# photodiode.net
KiCad netlist of a schematic drawn in EAGLE
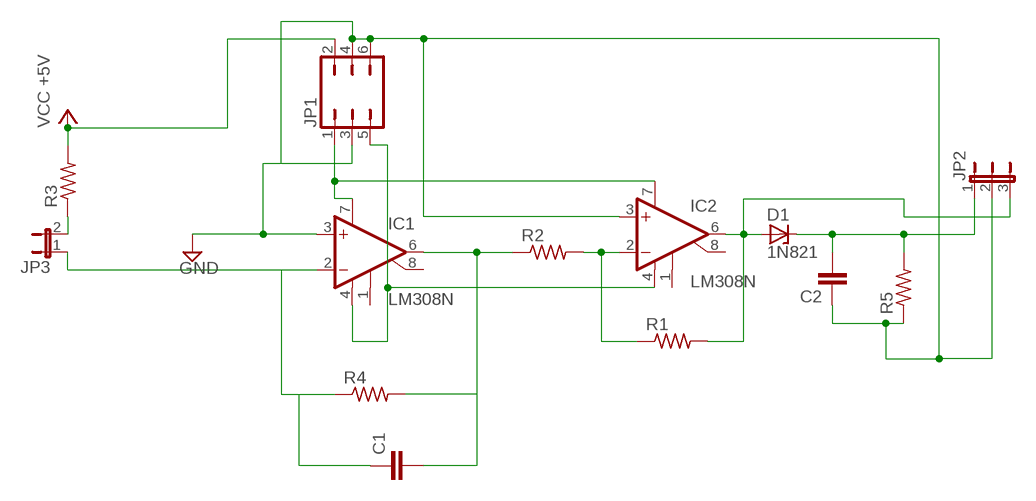
[diagram p0: schematic, sheet 1]

(export (version "E")
  (design (tool "Eeschema 10.0.6"))
  (components
    (comp (ref "C1")
      (value "C-EU025-024X044")
      (footprint "eagle-import:C025-024X044")
      (libsource (lib "eagle-import") (part "C-EU025-024X044"))
    )
    (comp (ref "C2")
      (value "C-EU025-024X044")
      (footprint "eagle-import:C025-024X044")
      (libsource (lib "eagle-import") (part "C-EU025-024X044"))
    )
    (comp (ref "D1")
      (value "1N821")
      (footprint "eagle-import:DO35Z10")
      (libsource (lib "eagle-import") (part "1N821"))
    )
    (comp (ref "IC1")
      (value "LM308N")
      (footprint "eagle-import:DIL08")
      (libsource (lib "eagle-import") (part "LM308N"))
    )
    (comp (ref "IC2")
      (value "LM308N")
      (footprint "eagle-import:DIL08")
      (libsource (lib "eagle-import") (part "LM308N"))
    )
    (comp (ref "JP1")
      (value "JP3Q")
      (footprint "eagle-import:JP3Q")
      (libsource (lib "eagle-import") (part "JP3Q"))
    )
    (comp (ref "JP2")
      (value "JP2E")
      (footprint "eagle-import:JP2")
      (libsource (lib "eagle-import") (part "JP2E"))
    )
    (comp (ref "JP3")
      (value "JP1E")
      (footprint "eagle-import:JP1")
      (libsource (lib "eagle-import") (part "JP1E"))
    )
    (comp (ref "R1")
      (value "R-US_0207/10")
      (footprint "eagle-import:0207_10")
      (libsource (lib "eagle-import") (part "R-US_0207/10"))
    )
    (comp (ref "R2")
      (value "R-US_0207/10")
      (footprint "eagle-import:0207_10")
      (libsource (lib "eagle-import") (part "R-US_0207/10"))
    )
    (comp (ref "R3")
      (value "R-US_0207/10")
      (footprint "eagle-import:0207_10")
      (libsource (lib "eagle-import") (part "R-US_0207/10"))
    )
    (comp (ref "R4")
      (value "R-US_0207/10")
      (footprint "eagle-import:0207_10")
      (libsource (lib "eagle-import") (part "R-US_0207/10"))
    )
    (comp (ref "R5")
      (value "R-US_0207/10")
      (footprint "eagle-import:0207_10")
      (libsource (lib "eagle-import") (part "R-US_0207/10"))
    )
  )
  (nets
    (net (code "1") (name "GND") (class "Default")
      (node (ref "C2") (pin "1") (pinfunction "1_1") (pintype "passive"))
      (node (ref "IC1") (pin "3") (pinfunction "+IN_3") (pintype "input"))
      (node (ref "IC2") (pin "3") (pinfunction "+IN_3") (pintype "input"))
      (node (ref "JP1") (pin "3") (pinfunction "3_3") (pintype "passive"))
      (node (ref "JP1") (pin "4") (pinfunction "4_4") (pintype "passive"))
      (node (ref "JP1") (pin "6") (pinfunction "6_6") (pintype "passive"))
      (node (ref "JP2") (pin "2") (pinfunction "2_2") (pintype "passive"))
      (node (ref "R5") (pin "1") (pinfunction "1_1") (pintype "passive"))
    )
    (net (code "2") (name "Net-(C2-Pad2)") (class "Default")
      (node (ref "C2") (pin "2") (pinfunction "2_2") (pintype "passive"))
      (node (ref "D1") (pin "C") (pinfunction "C_C") (pintype "passive"))
      (node (ref "JP2") (pin "1") (pinfunction "1_1") (pintype "passive"))
      (node (ref "R5") (pin "2") (pinfunction "2_2") (pintype "passive"))
    )
    (net (code "3") (name "Net-(IC1--IN)") (class "Default")
      (node (ref "C1") (pin "1") (pinfunction "1_1") (pintype "passive"))
      (node (ref "IC1") (pin "2") (pinfunction "-IN_2") (pintype "input"))
      (node (ref "JP3") (pin "1") (pinfunction "1_1") (pintype "passive"))
      (node (ref "R4") (pin "1") (pinfunction "1_1") (pintype "passive"))
    )
    (net (code "4") (name "Net-(IC1-OUT)") (class "Default")
      (node (ref "C1") (pin "2") (pinfunction "2_2") (pintype "passive"))
      (node (ref "IC1") (pin "6") (pinfunction "OUT_6") (pintype "output"))
      (node (ref "R2") (pin "1") (pinfunction "1_1") (pintype "passive"))
      (node (ref "R4") (pin "2") (pinfunction "2_2") (pintype "passive"))
    )
    (net (code "5") (name "Net-(IC1-V+)") (class "Default")
      (node (ref "IC1") (pin "7") (pinfunction "V+_7") (pintype "power_in"))
      (node (ref "IC2") (pin "7") (pinfunction "V+_7") (pintype "power_in"))
      (node (ref "JP1") (pin "1") (pinfunction "1_1") (pintype "passive"))
    )
    (net (code "6") (name "Net-(IC1-V-)") (class "Default")
      (node (ref "IC1") (pin "4") (pinfunction "V-_4") (pintype "power_in"))
      (node (ref "IC2") (pin "4") (pinfunction "V-_4") (pintype "power_in"))
      (node (ref "JP1") (pin "5") (pinfunction "5_5") (pintype "passive"))
    )
    (net (code "7") (name "Net-(IC2--IN)") (class "Default")
      (node (ref "IC2") (pin "2") (pinfunction "-IN_2") (pintype "input"))
      (node (ref "R1") (pin "1") (pinfunction "1_1") (pintype "passive"))
      (node (ref "R2") (pin "2") (pinfunction "2_2") (pintype "passive"))
    )
    (net (code "8") (name "Net-(IC2-OUT)") (class "Default")
      (node (ref "D1") (pin "A") (pinfunction "A_A") (pintype "passive"))
      (node (ref "IC2") (pin "6") (pinfunction "OUT_6") (pintype "output"))
      (node (ref "JP2") (pin "3") (pinfunction "3_3") (pintype "passive"))
      (node (ref "R1") (pin "2") (pinfunction "2_2") (pintype "passive"))
    )
    (net (code "9") (name "Net-(JP3-Pad2)") (class "Default")
      (node (ref "JP3") (pin "2") (pinfunction "2_2") (pintype "passive"))
      (node (ref "R3") (pin "1") (pinfunction "1_1") (pintype "passive"))
    )
    (net (code "10") (name "VCC +5V") (class "Default")
      (node (ref "JP1") (pin "2") (pinfunction "2_2") (pintype "passive"))
      (node (ref "R3") (pin "2") (pinfunction "2_2") (pintype "passive"))
    )
    (net (code "11") (name "unconnected-(IC1-CMP1-Pad1)") (class "Default")
      (node (ref "IC1") (pin "1") (pinfunction "CMP1_1") (pintype "passive"))
    )
    (net (code "12") (name "unconnected-(IC1-CMP2-Pad8)") (class "Default")
      (node (ref "IC1") (pin "8") (pinfunction "CMP2_8") (pintype "passive"))
    )
    (net (code "13") (name "unconnected-(IC2-CMP1-Pad1)") (class "Default")
      (node (ref "IC2") (pin "1") (pinfunction "CMP1_1") (pintype "passive"))
    )
    (net (code "14") (name "unconnected-(IC2-CMP2-Pad8)") (class "Default")
      (node (ref "IC2") (pin "8") (pinfunction "CMP2_8") (pintype "passive"))
    )
  )
)
